# Supply.net
KiCad netlist of a schematic drawn in Altium Designer
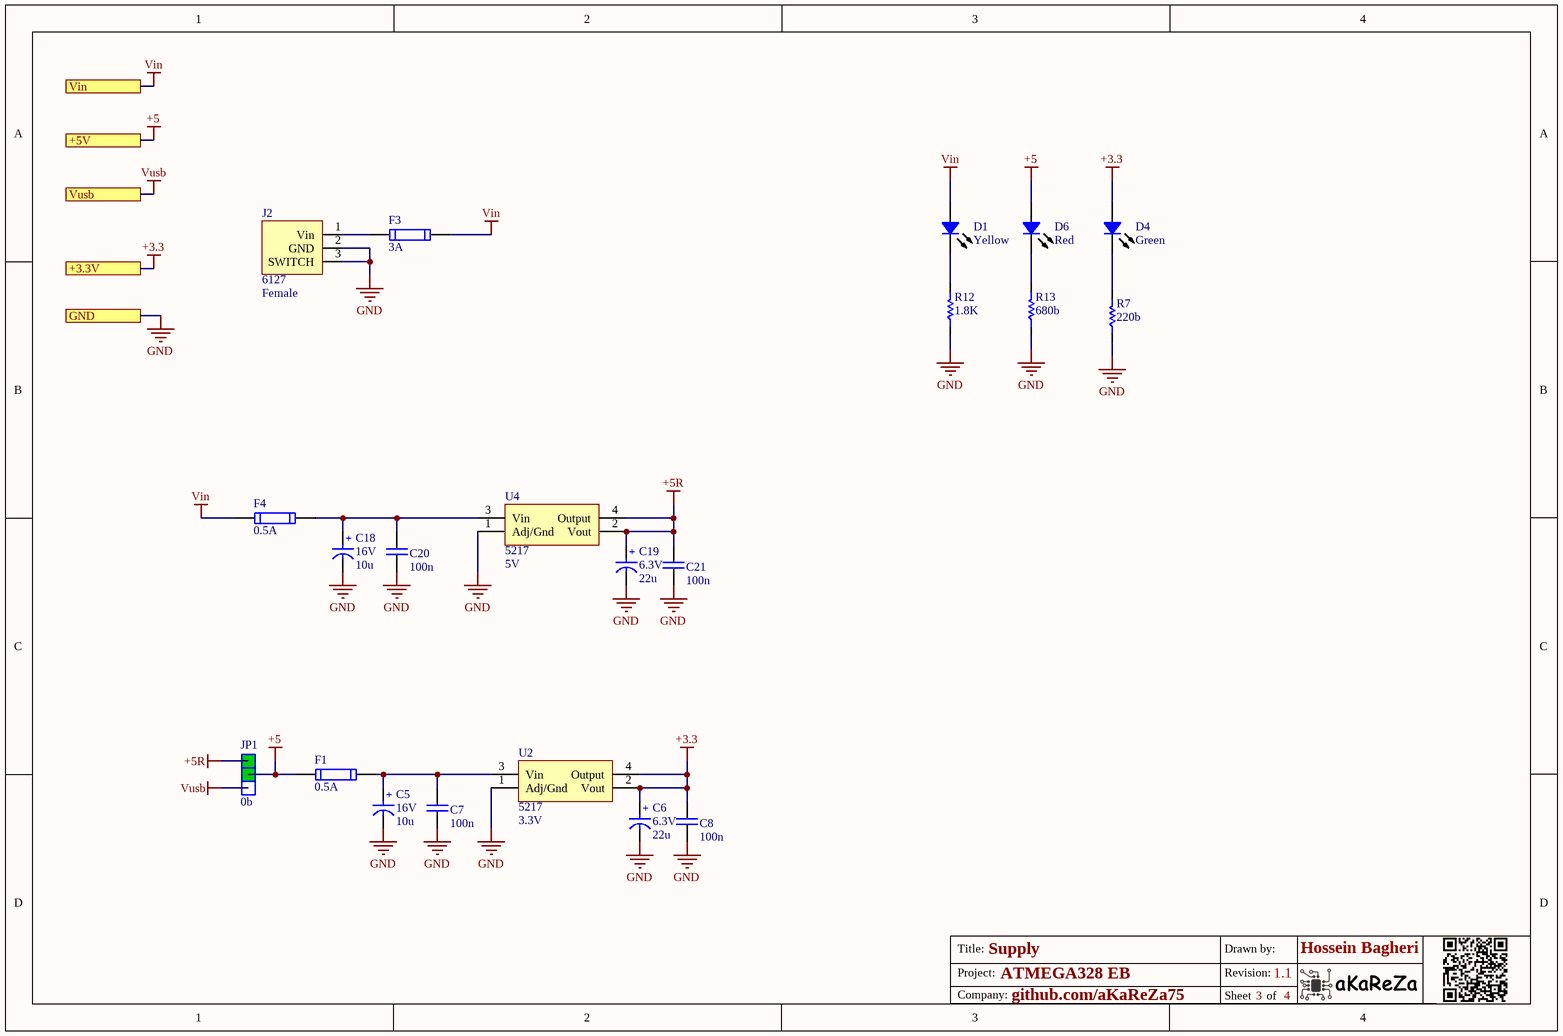
[diagram p0: Supply.SchDoc]

(export (version "E")
  (design (tool "Eeschema 10.0.6"))
  (components
    (comp (ref "C5")
      (value "10u")
      (footprint "SMT_C_Tantalum_A")
      (description "Tantalum Capacitor,TAJ Series-SMD")
      (fields (field (name "RATING") "16V") (field (name "VALIDATION") "Valid"))
      (libsource (lib "aKaReZa") (part "Cap_Tantalum"))
    )
    (comp (ref "C6")
      (value "22u")
      (footprint "SMT_C_Tantalum_A")
      (description "Tantalum Capacitor,TAJ Series-SMD")
      (fields (field (name "RATING") "6.3V") (field (name "VALIDATION") "Valid"))
      (libsource (lib "aKaReZa") (part "Cap_Tantalum"))
    )
    (comp (ref "C7")
      (value "100n")
      (footprint "CAP 1206/3216")
      (description "Bipolar ceramic capacitor SMD")
      (fields (field (name "VALIDATION") "Valid"))
      (libsource (lib "aKaReZa") (part "Cap_Multi_SMD_100nF_1206"))
    )
    (comp (ref "C8")
      (value "100n")
      (footprint "CAP 1206/3216")
      (description "Bipolar ceramic capacitor SMD")
      (fields (field (name "VALIDATION") "Valid"))
      (libsource (lib "aKaReZa") (part "Cap_Multi_SMD_100nF_1206"))
    )
    (comp (ref "C18")
      (value "10u")
      (footprint "SMT_C_Tantalum_A")
      (description "Tantalum Capacitor,TAJ Series-SMD")
      (fields (field (name "RATING") "16V") (field (name "VALIDATION") "Valid"))
      (libsource (lib "aKaReZa") (part "Cap_Tantalum"))
    )
    (comp (ref "C19")
      (value "22u")
      (footprint "SMT_C_Tantalum_A")
      (description "Tantalum Capacitor,TAJ Series-SMD")
      (fields (field (name "RATING") "6.3V") (field (name "VALIDATION") "Valid"))
      (libsource (lib "aKaReZa") (part "Cap_Tantalum"))
    )
    (comp (ref "C20")
      (value "100n")
      (footprint "CAP 1206/3216")
      (description "Bipolar ceramic capacitor SMD")
      (fields (field (name "VALIDATION") "Valid"))
      (libsource (lib "aKaReZa") (part "Cap_Multi_SMD_100nF_1206"))
    )
    (comp (ref "C21")
      (value "100n")
      (footprint "CAP 1206/3216")
      (description "Bipolar ceramic capacitor SMD")
      (fields (field (name "VALIDATION") "Valid"))
      (libsource (lib "aKaReZa") (part "Cap_Multi_SMD_100nF_1206"))
    )
    (comp (ref "D1")
      (value "Yellow")
      (footprint "LED 0805/2012 YELLOW")
      (description "LED")
      (fields (field (name "VALIDATION") "Valid"))
      (libsource (lib "aKaReZa") (part "Semi_LED_SMD"))
    )
    (comp (ref "D4")
      (value "Green")
      (footprint "LED 0805/2012 GREEN")
      (description "LED")
      (fields (field (name "VALIDATION") "Valid"))
      (libsource (lib "aKaReZa") (part "Semi_LED_SMD"))
    )
    (comp (ref "D6")
      (value "Red")
      (footprint "LED 0805/2012 RED")
      (description "LED")
      (fields (field (name "VALIDATION") "Valid"))
      (libsource (lib "aKaReZa") (part "Semi_LED_SMD"))
    )
    (comp (ref "F1")
      (value "0.5A")
      (footprint "1206_F")
      (description "Short circiut  protection")
      (fields (field (name "VALIDATION") "Valid"))
      (libsource (lib "aKaReZa") (part "Other_Elec_Fuse_SMD"))
    )
    (comp (ref "F3")
      (value "3A")
      (footprint "1206_F")
      (description "Short circiut  protection")
      (fields (field (name "VALIDATION") "Valid"))
      (libsource (lib "aKaReZa") (part "Other_Elec_Fuse_SMD"))
    )
    (comp (ref "F4")
      (value "0.5A")
      (footprint "1206_F")
      (description "Short circiut  protection")
      (fields (field (name "VALIDATION") "Valid"))
      (libsource (lib "aKaReZa") (part "Other_Elec_Fuse_SMD"))
    )
    (comp (ref "J2")
      (value "Female")
      (footprint "Power Jack BIG")
      (description "Power Jack")
      (fields (field (name "INFLOW") "6127") (field (name "VALIDATION") "Valid"))
      (libsource (lib "aKaReZa") (part "Con_Power_Jack"))
    )
    (comp (ref "JP1")
      (value "0b")
      (footprint "jumper selector")
      (description "Jumper Selector")
      (fields (field (name "VALIDATION") "NT"))
      (libsource (lib "aKaReZa") (part "SW_Other_JSelector_Dip"))
    )
    (comp (ref "R7")
      (value "220b")
      (footprint "RES 0805 (2012X06L)")
      (description "Resistor")
      (fields (field (name "VALIDATION") "Valid"))
      (libsource (lib "aKaReZa") (part "Res_SMD_0805"))
    )
    (comp (ref "R12")
      (value "1.8K")
      (footprint "RES 0805 (2012X06L)")
      (description "Resistor")
      (fields (field (name "VALIDATION") "Valid"))
      (libsource (lib "aKaReZa") (part "Res_SMD_0805"))
    )
    (comp (ref "R13")
      (value "680b")
      (footprint "RES 0805 (2012X06L)")
      (description "Resistor")
      (fields (field (name "VALIDATION") "Valid"))
      (libsource (lib "aKaReZa") (part "Res_SMD_0805"))
    )
    (comp (ref "U2")
      (value "3.3V")
      (footprint "SOT223_M")
      (description "1'A Positive voltage regulator")
      (fields (field (name "INFLOW") "5217") (field (name "VALIDATION") "Valid"))
      (libsource (lib "aKaReZa") (part "IC_Reg_AMS1117_3.3"))
    )
    (comp (ref "U4")
      (value "5V")
      (footprint "SOT223_M")
      (description "1'A Positive voltage regulator")
      (fields (field (name "INFLOW") "5217") (field (name "VALIDATION") "Valid"))
      (libsource (lib "aKaReZa") (part "IC_Reg_AMS1117_3.3"))
    )
  )
  (nets
    (net (code "1") (name "+3.3") (class "Default")
      (node (ref "C6") (pin "1") (pinfunction "+_1") (pintype "passive"))
      (node (ref "C8") (pin "1") (pinfunction "1_1") (pintype "passive"))
      (node (ref "D4") (pin "1") (pinfunction "1_1") (pintype "passive"))
      (node (ref "U2") (pin "2") (pinfunction "Vout_2") (pintype "passive"))
      (node (ref "U2") (pin "4") (pinfunction "Output_4") (pintype "passive"))
    )
    (net (code "2") (name "+5") (class "Default")
      (node (ref "D6") (pin "1") (pinfunction "1_1") (pintype "passive"))
      (node (ref "F1") (pin "1") (pinfunction "1_1") (pintype "passive"))
      (node (ref "JP1") (pin "2") (pinfunction "2_2") (pintype "passive"))
    )
    (net (code "3") (name "+5R") (class "Default")
      (node (ref "C19") (pin "1") (pinfunction "+_1") (pintype "passive"))
      (node (ref "C21") (pin "1") (pinfunction "1_1") (pintype "passive"))
      (node (ref "JP1") (pin "1") (pinfunction "1_1") (pintype "passive"))
      (node (ref "U4") (pin "2") (pinfunction "Vout_2") (pintype "passive"))
      (node (ref "U4") (pin "4") (pinfunction "Output_4") (pintype "passive"))
    )
    (net (code "4") (name "GND") (class "Default")
      (node (ref "C18") (pin "2") (pinfunction "-_2") (pintype "passive"))
      (node (ref "C19") (pin "2") (pinfunction "-_2") (pintype "passive"))
      (node (ref "C20") (pin "2") (pinfunction "2_2") (pintype "passive"))
      (node (ref "C21") (pin "2") (pinfunction "2_2") (pintype "passive"))
      (node (ref "C5") (pin "2") (pinfunction "-_2") (pintype "passive"))
      (node (ref "C6") (pin "2") (pinfunction "-_2") (pintype "passive"))
      (node (ref "C7") (pin "2") (pinfunction "2_2") (pintype "passive"))
      (node (ref "C8") (pin "2") (pinfunction "2_2") (pintype "passive"))
      (node (ref "J2") (pin "2") (pinfunction "GND_2") (pintype "passive"))
      (node (ref "J2") (pin "3") (pinfunction "SWITCH_3") (pintype "passive"))
      (node (ref "R12") (pin "1") (pinfunction "1_1") (pintype "passive"))
      (node (ref "R13") (pin "1") (pinfunction "1_1") (pintype "passive"))
      (node (ref "R7") (pin "1") (pinfunction "1_1") (pintype "passive"))
      (node (ref "U2") (pin "1") (pinfunction "Adj/Gnd_1") (pintype "passive"))
      (node (ref "U4") (pin "1") (pinfunction "Adj/Gnd_1") (pintype "passive"))
    )
    (net (code "5") (name "Net-(C5-+)") (class "Default")
      (node (ref "C5") (pin "1") (pinfunction "+_1") (pintype "passive"))
      (node (ref "C7") (pin "1") (pinfunction "1_1") (pintype "passive"))
      (node (ref "F1") (pin "2") (pinfunction "2_2") (pintype "passive"))
      (node (ref "U2") (pin "3") (pinfunction "Vin_3") (pintype "passive"))
    )
    (net (code "6") (name "Net-(C18-+)") (class "Default")
      (node (ref "C18") (pin "1") (pinfunction "+_1") (pintype "passive"))
      (node (ref "C20") (pin "1") (pinfunction "1_1") (pintype "passive"))
      (node (ref "F4") (pin "2") (pinfunction "2_2") (pintype "passive"))
      (node (ref "U4") (pin "3") (pinfunction "Vin_3") (pintype "passive"))
    )
    (net (code "7") (name "Net-(D1-Pad2)") (class "Default")
      (node (ref "D1") (pin "2") (pinfunction "2_2") (pintype "passive"))
      (node (ref "R12") (pin "2") (pinfunction "2_2") (pintype "passive"))
    )
    (net (code "8") (name "Net-(D4-Pad2)") (class "Default")
      (node (ref "D4") (pin "2") (pinfunction "2_2") (pintype "passive"))
      (node (ref "R7") (pin "2") (pinfunction "2_2") (pintype "passive"))
    )
    (net (code "9") (name "Net-(D6-Pad2)") (class "Default")
      (node (ref "D6") (pin "2") (pinfunction "2_2") (pintype "passive"))
      (node (ref "R13") (pin "2") (pinfunction "2_2") (pintype "passive"))
    )
    (net (code "10") (name "Net-(J2-Vin)") (class "Default")
      (node (ref "F3") (pin "1") (pinfunction "1_1") (pintype "passive"))
      (node (ref "J2") (pin "1") (pinfunction "Vin_1") (pintype "passive"))
    )
    (net (code "11") (name "Vin") (class "Default")
      (node (ref "D1") (pin "1") (pinfunction "1_1") (pintype "passive"))
      (node (ref "F3") (pin "2") (pinfunction "2_2") (pintype "passive"))
      (node (ref "F4") (pin "1") (pinfunction "1_1") (pintype "passive"))
    )
    (net (code "12") (name "Vusb") (class "Default")
      (node (ref "JP1") (pin "3") (pinfunction "3_3") (pintype "passive"))
    )
  )
)
